# Sheet1.net
KiCad netlist of a schematic drawn in Altium Designer
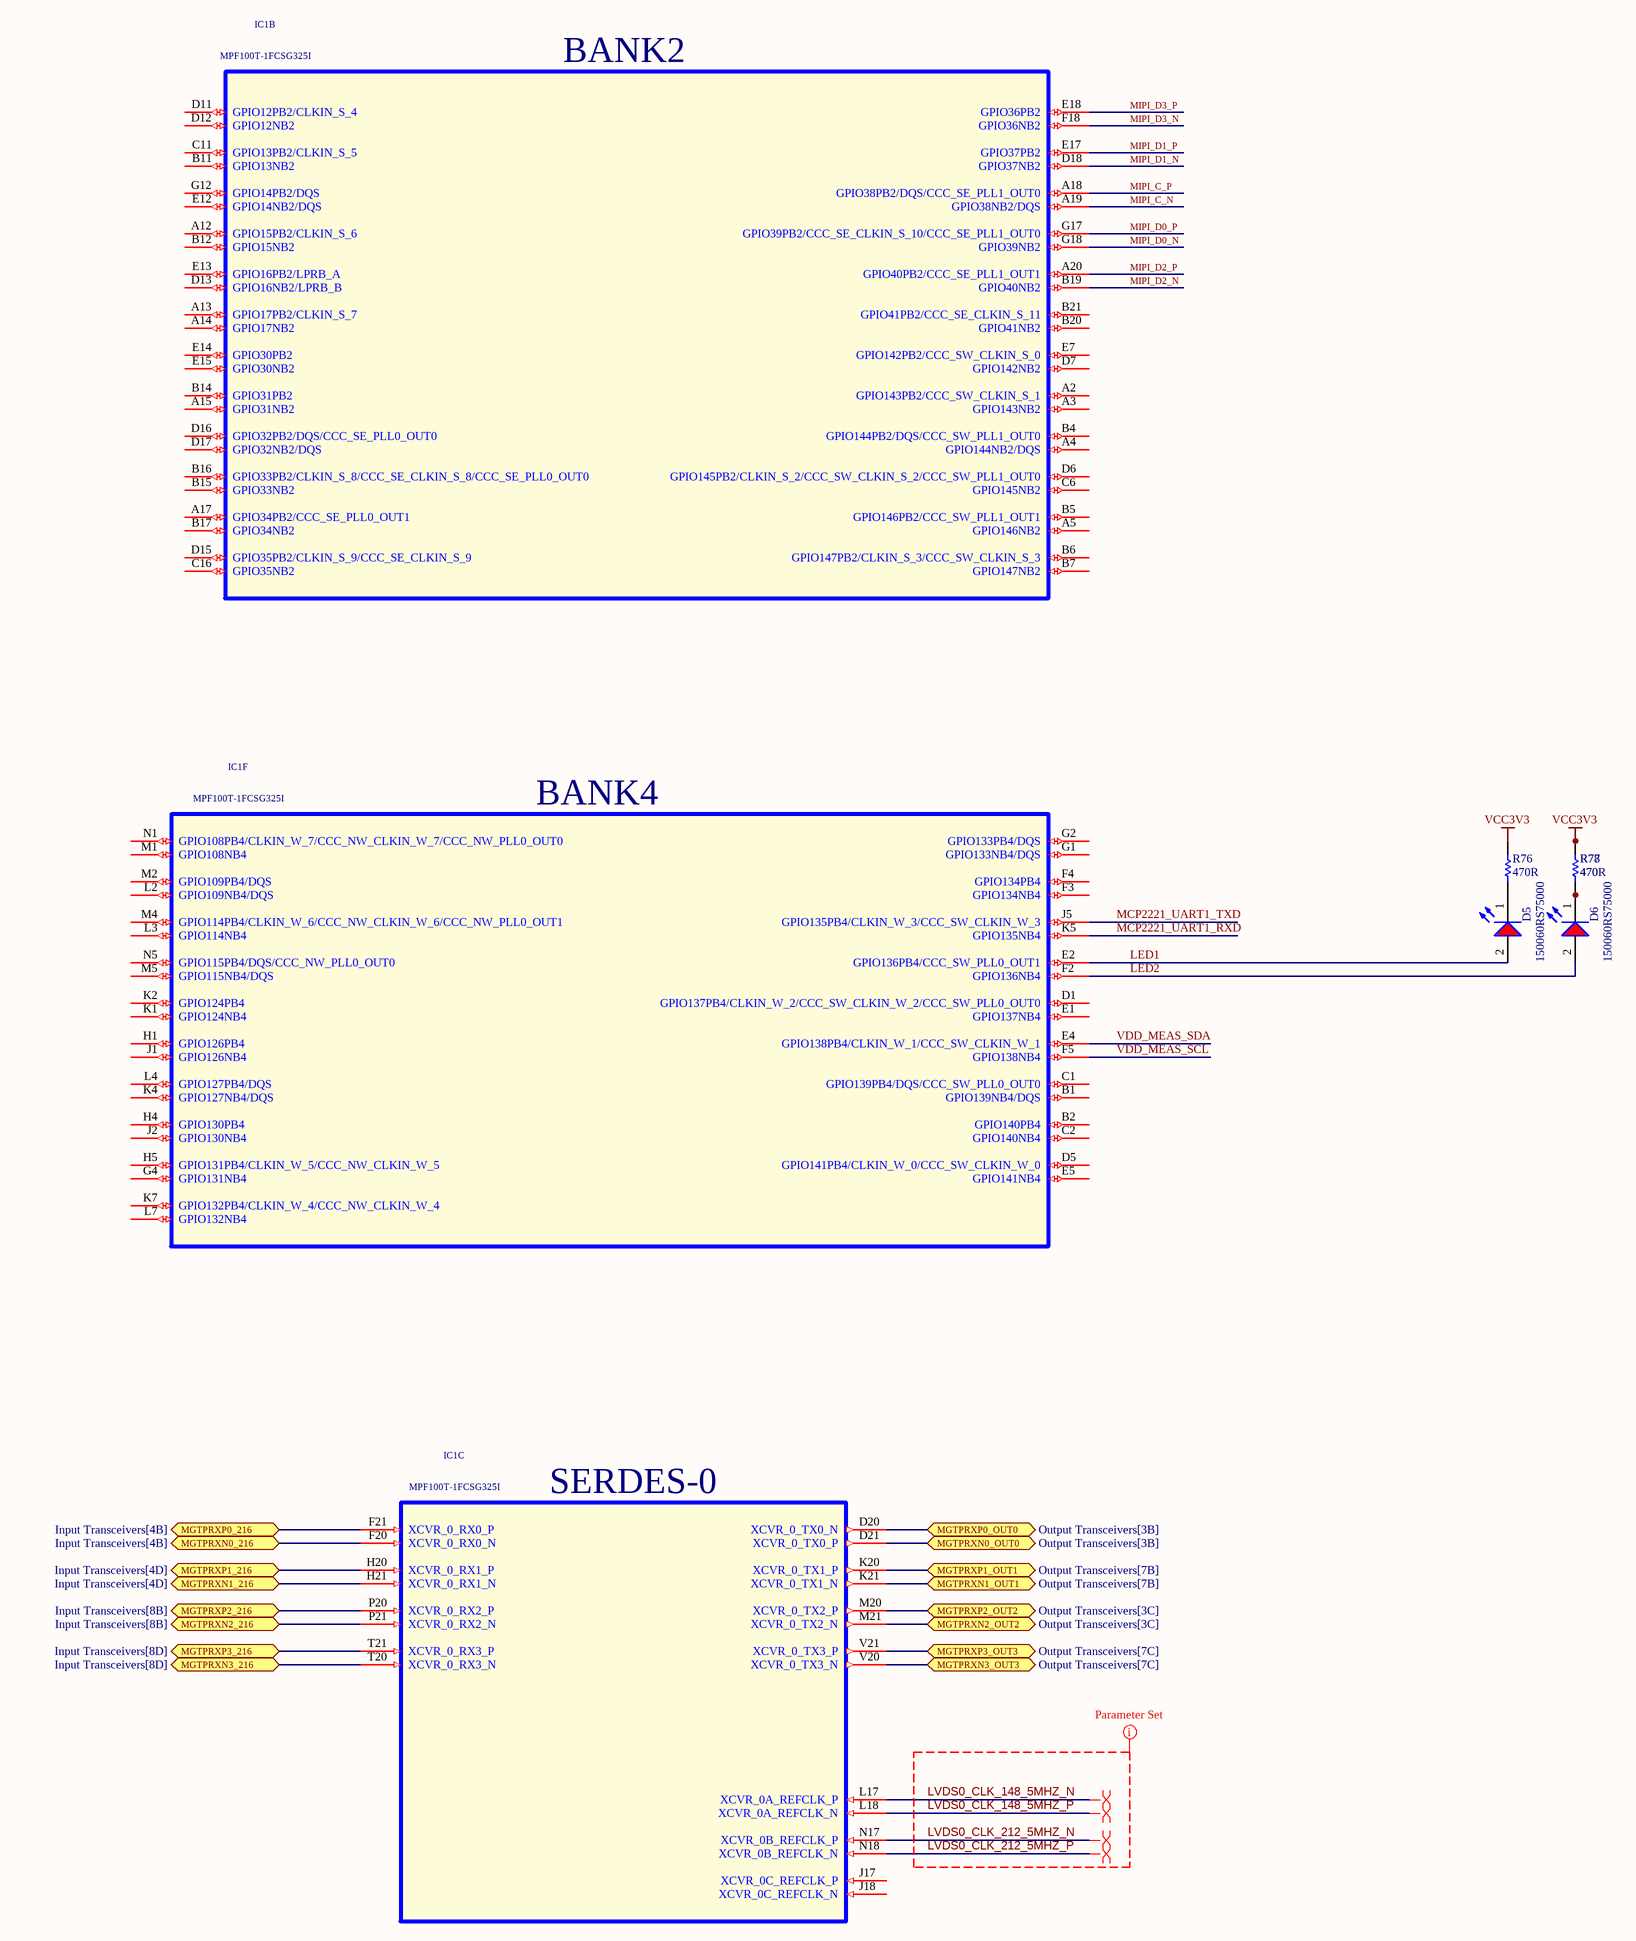
[diagram p0: Sheet1.schdoc]

(export (version "E")
  (design (tool "Eeschema 10.0.6"))
  (components
    (comp (ref "D5")
      (value "150060RS75000")
      (footprint "WL-SMCW_0603_150060xx75000")
      (description "LED Low-Power Uni-Color Red 630nm 2V 2-Pin Chip 0603(1608Metric) T/R")
      (libsource (lib "Altium Content Vault") (part "LED_Red_2A-1K"))
    )
    (comp (ref "D6")
      (value "150060RS75000")
      (footprint "WL-SMCW_0603_150060xx75000")
      (description "LED Low-Power Uni-Color Red 630nm 2V 2-Pin Chip 0603(1608Metric) T/R")
      (libsource (lib "Altium Content Vault") (part "LED_Red_2A-1K"))
    )
    (comp (ref "IC1")
      (value "MPF100T-1FCSG325I")
      (footprint "PCB_Display_Doru:MPF100T-1FCSG325I")
      (fields (field (name "PART_NUMBER") "J00001"))
      (libsource (lib "PCB_Display_Doru") (part "MPF100T-1FCSG325I"))
    )
    (comp (ref "R76")
      (value "470R")
      (footprint "RESC1005X40X25ML05T10")
      (fields (field (name "PART NUMBER") "RC0402FR-07470RL") (field (name "MANUFACTURER") "Yageo / Phycomp"))
      (libsource (lib "Altium Content Vault") (part "RES"))
    )
    (comp (ref "R77")
      (value "470")
      (footprint "RESC1005X40X25ML05T10")
      (fields (field (name "PART NUMBER") "RC0402FR-07470RL") (field (name "MANUFACTURER") "Yageo / Phycomp"))
      (libsource (lib "Altium Content Vault") (part "RES"))
    )
    (comp (ref "R78")
      (value "470R")
      (footprint "RESC1005X40X25ML05T10")
      (fields (field (name "PART NUMBER") "RC0402FR-07470RL") (field (name "MANUFACTURER") "Yageo / Phycomp"))
      (libsource (lib "Altium Content Vault") (part "RES"))
    )
  )
  (nets
    (net (code "1") (name "/LED1") (class "Default")
      (node (ref "D5") (pin "2") (pinfunction "A_2") (pintype "passive"))
      (node (ref "IC1") (pin "E2") (pinfunction "GPIO136PB4/CCC_SW_PLL0_OUT1_E2") (pintype "bidirectional"))
    )
    (net (code "2") (name "/LED2") (class "Default")
      (node (ref "D6") (pin "2") (pinfunction "A_2") (pintype "passive"))
      (node (ref "IC1") (pin "F2") (pinfunction "GPIO136NB4_F2") (pintype "bidirectional"))
    )
    (net (code "3") (name "/LVDS0_CLK_148_5MHZ_N") (class "Default")
      (node (ref "IC1") (pin "L17") (pinfunction "XCVR_0A_REFCLK_P_L17") (pintype "input"))
    )
    (net (code "4") (name "/LVDS0_CLK_148_5MHZ_P") (class "Default")
      (node (ref "IC1") (pin "L18") (pinfunction "XCVR_0A_REFCLK_N_L18") (pintype "input"))
    )
    (net (code "5") (name "/LVDS0_CLK_212_5MHZ_N") (class "Default")
      (node (ref "IC1") (pin "N17") (pinfunction "XCVR_0B_REFCLK_P_N17") (pintype "input"))
    )
    (net (code "6") (name "/LVDS0_CLK_212_5MHZ_P") (class "Default")
      (node (ref "IC1") (pin "N18") (pinfunction "XCVR_0B_REFCLK_N_N18") (pintype "input"))
    )
    (net (code "7") (name "/MCP2221_UART1_RXD") (class "Default")
      (node (ref "IC1") (pin "K5") (pinfunction "GPIO135NB4_K5") (pintype "bidirectional"))
    )
    (net (code "8") (name "/MCP2221_UART1_TXD") (class "Default")
      (node (ref "IC1") (pin "J5") (pinfunction "GPIO135PB4/CLKIN_W_3/CCC_SW_CLKIN_W_3_J5") (pintype "bidirectional"))
    )
    (net (code "9") (name "/MGTPRXN0_216") (class "Default")
      (node (ref "IC1") (pin "F20") (pinfunction "XCVR_0_RX0_N_F20") (pintype "input"))
    )
    (net (code "10") (name "/MGTPRXN0_OUT0") (class "Default")
      (node (ref "IC1") (pin "D21") (pinfunction "XCVR_0_TX0_P_D21") (pintype "output"))
    )
    (net (code "11") (name "/MGTPRXN1_216") (class "Default")
      (node (ref "IC1") (pin "H21") (pinfunction "XCVR_0_RX1_N_H21") (pintype "input"))
    )
    (net (code "12") (name "/MGTPRXN1_OUT1") (class "Default")
      (node (ref "IC1") (pin "K21") (pinfunction "XCVR_0_TX1_N_K21") (pintype "output"))
    )
    (net (code "13") (name "/MGTPRXN2_216") (class "Default")
      (node (ref "IC1") (pin "P21") (pinfunction "XCVR_0_RX2_N_P21") (pintype "input"))
    )
    (net (code "14") (name "/MGTPRXN2_OUT2") (class "Default")
      (node (ref "IC1") (pin "M21") (pinfunction "XCVR_0_TX2_N_M21") (pintype "output"))
    )
    (net (code "15") (name "/MGTPRXN3_216") (class "Default")
      (node (ref "IC1") (pin "T20") (pinfunction "XCVR_0_RX3_N_T20") (pintype "input"))
    )
    (net (code "16") (name "/MGTPRXN3_OUT3") (class "Default")
      (node (ref "IC1") (pin "V20") (pinfunction "XCVR_0_TX3_N_V20") (pintype "output"))
    )
    (net (code "17") (name "/MGTPRXP0_216") (class "Default")
      (node (ref "IC1") (pin "F21") (pinfunction "XCVR_0_RX0_P_F21") (pintype "input"))
    )
    (net (code "18") (name "/MGTPRXP0_OUT0") (class "Default")
      (node (ref "IC1") (pin "D20") (pinfunction "XCVR_0_TX0_N_D20") (pintype "output"))
    )
    (net (code "19") (name "/MGTPRXP1_216") (class "Default")
      (node (ref "IC1") (pin "H20") (pinfunction "XCVR_0_RX1_P_H20") (pintype "input"))
    )
    (net (code "20") (name "/MGTPRXP1_OUT1") (class "Default")
      (node (ref "IC1") (pin "K20") (pinfunction "XCVR_0_TX1_P_K20") (pintype "output"))
    )
    (net (code "21") (name "/MGTPRXP2_216") (class "Default")
      (node (ref "IC1") (pin "P20") (pinfunction "XCVR_0_RX2_P_P20") (pintype "input"))
    )
    (net (code "22") (name "/MGTPRXP2_OUT2") (class "Default")
      (node (ref "IC1") (pin "M20") (pinfunction "XCVR_0_TX2_P_M20") (pintype "output"))
    )
    (net (code "23") (name "/MGTPRXP3_216") (class "Default")
      (node (ref "IC1") (pin "T21") (pinfunction "XCVR_0_RX3_P_T21") (pintype "input"))
    )
    (net (code "24") (name "/MGTPRXP3_OUT3") (class "Default")
      (node (ref "IC1") (pin "V21") (pinfunction "XCVR_0_TX3_P_V21") (pintype "output"))
    )
    (net (code "25") (name "/MIPI_C_N") (class "Default")
      (node (ref "IC1") (pin "A19") (pinfunction "GPIO38NB2/DQS_A19") (pintype "bidirectional"))
    )
    (net (code "26") (name "/MIPI_C_P") (class "Default")
      (node (ref "IC1") (pin "A18") (pinfunction "GPIO38PB2/DQS/CCC_SE_PLL1_OUT0_A18") (pintype "bidirectional"))
    )
    (net (code "27") (name "/MIPI_D0_N") (class "Default")
      (node (ref "IC1") (pin "G18") (pinfunction "GPIO39NB2_G18") (pintype "bidirectional"))
    )
    (net (code "28") (name "/MIPI_D0_P") (class "Default")
      (node (ref "IC1") (pin "G17") (pinfunction "GPIO39PB2/CCC_SE_CLKIN_S_10/CCC_SE_PLL1_OUT0_G17") (pintype "bidirectional"))
    )
    (net (code "29") (name "/MIPI_D1_N") (class "Default")
      (node (ref "IC1") (pin "D18") (pinfunction "GPIO37NB2_D18") (pintype "bidirectional"))
    )
    (net (code "30") (name "/MIPI_D1_P") (class "Default")
      (node (ref "IC1") (pin "E17") (pinfunction "GPIO37PB2_E17") (pintype "bidirectional"))
    )
    (net (code "31") (name "/MIPI_D2_N") (class "Default")
      (node (ref "IC1") (pin "B19") (pinfunction "GPIO40NB2_B19") (pintype "bidirectional"))
    )
    (net (code "32") (name "/MIPI_D2_P") (class "Default")
      (node (ref "IC1") (pin "A20") (pinfunction "GPIO40PB2/CCC_SE_PLL1_OUT1_A20") (pintype "bidirectional"))
    )
    (net (code "33") (name "/MIPI_D3_N") (class "Default")
      (node (ref "IC1") (pin "F18") (pinfunction "GPIO36NB2_F18") (pintype "bidirectional"))
    )
    (net (code "34") (name "/MIPI_D3_P") (class "Default")
      (node (ref "IC1") (pin "E18") (pinfunction "GPIO36PB2_E18") (pintype "bidirectional"))
    )
    (net (code "35") (name "/VDD_MEAS_SCL") (class "Default")
      (node (ref "IC1") (pin "F5") (pinfunction "GPIO138NB4_F5") (pintype "bidirectional"))
    )
    (net (code "36") (name "/VDD_MEAS_SDA") (class "Default")
      (node (ref "IC1") (pin "E4") (pinfunction "GPIO138PB4/CLKIN_W_1/CCC_SW_CLKIN_W_1_E4") (pintype "bidirectional"))
    )
    (net (code "37") (name "Net-(D5-K)") (class "Default")
      (node (ref "D5") (pin "1") (pinfunction "K_1") (pintype "passive"))
      (node (ref "R76") (pin "1") (pinfunction "1_1") (pintype "passive"))
    )
    (net (code "38") (name "Net-(D6-K)") (class "Default")
      (node (ref "D6") (pin "1") (pinfunction "K_1") (pintype "passive"))
      (node (ref "R77") (pin "1") (pinfunction "1_1") (pintype "passive"))
      (node (ref "R78") (pin "1") (pinfunction "1_1") (pintype "passive"))
    )
    (net (code "39") (name "VCC3V3") (class "Default")
      (node (ref "R76") (pin "2") (pinfunction "2_2") (pintype "passive"))
      (node (ref "R77") (pin "2") (pinfunction "2_2") (pintype "passive"))
      (node (ref "R78") (pin "2") (pinfunction "2_2") (pintype "passive"))
    )
    (net (code "40") (name "unconnected-(IC1B-GPIO12NB2-PadD12)") (class "Default")
      (node (ref "IC1") (pin "D12") (pinfunction "GPIO12NB2_D12") (pintype "bidirectional"))
    )
    (net (code "41") (name "unconnected-(IC1B-GPIO12PB2{slash}CLKIN_S_4-PadD11)") (class "Default")
      (node (ref "IC1") (pin "D11") (pinfunction "GPIO12PB2/CLKIN_S_4_D11") (pintype "bidirectional"))
    )
    (net (code "42") (name "unconnected-(IC1B-GPIO13NB2-PadB11)") (class "Default")
      (node (ref "IC1") (pin "B11") (pinfunction "GPIO13NB2_B11") (pintype "bidirectional"))
    )
    (net (code "43") (name "unconnected-(IC1B-GPIO13PB2{slash}CLKIN_S_5-PadC11)") (class "Default")
      (node (ref "IC1") (pin "C11") (pinfunction "GPIO13PB2/CLKIN_S_5_C11") (pintype "bidirectional"))
    )
    (net (code "44") (name "unconnected-(IC1B-GPIO14NB2{slash}DQS-PadE12)") (class "Default")
      (node (ref "IC1") (pin "E12") (pinfunction "GPIO14NB2/DQS_E12") (pintype "bidirectional"))
    )
    (net (code "45") (name "unconnected-(IC1B-GPIO14PB2{slash}DQS-PadG12)") (class "Default")
      (node (ref "IC1") (pin "G12") (pinfunction "GPIO14PB2/DQS_G12") (pintype "bidirectional"))
    )
    (net (code "46") (name "unconnected-(IC1B-GPIO15NB2-PadB12)") (class "Default")
      (node (ref "IC1") (pin "B12") (pinfunction "GPIO15NB2_B12") (pintype "bidirectional"))
    )
    (net (code "47") (name "unconnected-(IC1B-GPIO15PB2{slash}CLKIN_S_6-PadA12)") (class "Default")
      (node (ref "IC1") (pin "A12") (pinfunction "GPIO15PB2/CLKIN_S_6_A12") (pintype "bidirectional"))
    )
    (net (code "48") (name "unconnected-(IC1B-GPIO16NB2{slash}LPRB_B-PadD13)") (class "Default")
      (node (ref "IC1") (pin "D13") (pinfunction "GPIO16NB2/LPRB_B_D13") (pintype "bidirectional"))
    )
    (net (code "49") (name "unconnected-(IC1B-GPIO16PB2{slash}LPRB_A-PadE13)") (class "Default")
      (node (ref "IC1") (pin "E13") (pinfunction "GPIO16PB2/LPRB_A_E13") (pintype "bidirectional"))
    )
    (net (code "50") (name "unconnected-(IC1B-GPIO17NB2-PadA14)") (class "Default")
      (node (ref "IC1") (pin "A14") (pinfunction "GPIO17NB2_A14") (pintype "bidirectional"))
    )
    (net (code "51") (name "unconnected-(IC1B-GPIO17PB2{slash}CLKIN_S_7-PadA13)") (class "Default")
      (node (ref "IC1") (pin "A13") (pinfunction "GPIO17PB2/CLKIN_S_7_A13") (pintype "bidirectional"))
    )
    (net (code "52") (name "unconnected-(IC1B-GPIO30NB2-PadE15)") (class "Default")
      (node (ref "IC1") (pin "E15") (pinfunction "GPIO30NB2_E15") (pintype "bidirectional"))
    )
    (net (code "53") (name "unconnected-(IC1B-GPIO30PB2-PadE14)") (class "Default")
      (node (ref "IC1") (pin "E14") (pinfunction "GPIO30PB2_E14") (pintype "bidirectional"))
    )
    (net (code "54") (name "unconnected-(IC1B-GPIO31NB2-PadA15)") (class "Default")
      (node (ref "IC1") (pin "A15") (pinfunction "GPIO31NB2_A15") (pintype "bidirectional"))
    )
    (net (code "55") (name "unconnected-(IC1B-GPIO31PB2-PadB14)") (class "Default")
      (node (ref "IC1") (pin "B14") (pinfunction "GPIO31PB2_B14") (pintype "bidirectional"))
    )
    (net (code "56") (name "unconnected-(IC1B-GPIO32NB2{slash}DQS-PadD17)") (class "Default")
      (node (ref "IC1") (pin "D17") (pinfunction "GPIO32NB2/DQS_D17") (pintype "bidirectional"))
    )
    (net (code "57") (name "unconnected-(IC1B-GPIO32PB2{slash}DQS{slash}CCC_SE_PLL0_OUT0-PadD16)") (class "Default")
      (node (ref "IC1") (pin "D16") (pinfunction "GPIO32PB2/DQS/CCC_SE_PLL0_OUT0_D16") (pintype "bidirectional"))
    )
    (net (code "58") (name "unconnected-(IC1B-GPIO33NB2-PadB15)") (class "Default")
      (node (ref "IC1") (pin "B15") (pinfunction "GPIO33NB2_B15") (pintype "bidirectional"))
    )
    (net (code "59") (name "unconnected-(IC1B-GPIO33PB2{slash}CLKIN_S_8{slash}CCC_SE_CLKIN_S_8{slash}CCC_SE_PLL0_OUT0-PadB16)") (class "Default")
      (node (ref "IC1") (pin "B16") (pinfunction "GPIO33PB2/CLKIN_S_8/CCC_SE_CLKIN_S_8/CCC_SE_PLL0_OUT0_B16") (pintype "bidirectional"))
    )
    (net (code "60") (name "unconnected-(IC1B-GPIO34NB2-PadB17)") (class "Default")
      (node (ref "IC1") (pin "B17") (pinfunction "GPIO34NB2_B17") (pintype "bidirectional"))
    )
    (net (code "61") (name "unconnected-(IC1B-GPIO34PB2{slash}CCC_SE_PLL0_OUT1-PadA17)") (class "Default")
      (node (ref "IC1") (pin "A17") (pinfunction "GPIO34PB2/CCC_SE_PLL0_OUT1_A17") (pintype "bidirectional"))
    )
    (net (code "62") (name "unconnected-(IC1B-GPIO35NB2-PadC16)") (class "Default")
      (node (ref "IC1") (pin "C16") (pinfunction "GPIO35NB2_C16") (pintype "bidirectional"))
    )
    (net (code "63") (name "unconnected-(IC1B-GPIO35PB2{slash}CLKIN_S_9{slash}CCC_SE_CLKIN_S_9-PadD15)") (class "Default")
      (node (ref "IC1") (pin "D15") (pinfunction "GPIO35PB2/CLKIN_S_9/CCC_SE_CLKIN_S_9_D15") (pintype "bidirectional"))
    )
    (net (code "64") (name "unconnected-(IC1B-GPIO41NB2-PadB20)") (class "Default")
      (node (ref "IC1") (pin "B20") (pinfunction "GPIO41NB2_B20") (pintype "bidirectional"))
    )
    (net (code "65") (name "unconnected-(IC1B-GPIO41PB2{slash}CCC_SE_CLKIN_S_11-PadB21)") (class "Default")
      (node (ref "IC1") (pin "B21") (pinfunction "GPIO41PB2/CCC_SE_CLKIN_S_11_B21") (pintype "bidirectional"))
    )
    (net (code "66") (name "unconnected-(IC1B-GPIO142NB2-PadD7)") (class "Default")
      (node (ref "IC1") (pin "D7") (pinfunction "GPIO142NB2_D7") (pintype "bidirectional"))
    )
    (net (code "67") (name "unconnected-(IC1B-GPIO142PB2{slash}CCC_SW_CLKIN_S_0-PadE7)") (class "Default")
      (node (ref "IC1") (pin "E7") (pinfunction "GPIO142PB2/CCC_SW_CLKIN_S_0_E7") (pintype "bidirectional"))
    )
    (net (code "68") (name "unconnected-(IC1B-GPIO143NB2-PadA3)") (class "Default")
      (node (ref "IC1") (pin "A3") (pinfunction "GPIO143NB2_A3") (pintype "bidirectional"))
    )
    (net (code "69") (name "unconnected-(IC1B-GPIO143PB2{slash}CCC_SW_CLKIN_S_1-PadA2)") (class "Default")
      (node (ref "IC1") (pin "A2") (pinfunction "GPIO143PB2/CCC_SW_CLKIN_S_1_A2") (pintype "bidirectional"))
    )
    (net (code "70") (name "unconnected-(IC1B-GPIO144NB2{slash}DQS-PadA4)") (class "Default")
      (node (ref "IC1") (pin "A4") (pinfunction "GPIO144NB2/DQS_A4") (pintype "bidirectional"))
    )
    (net (code "71") (name "unconnected-(IC1B-GPIO144PB2{slash}DQS{slash}CCC_SW_PLL1_OUT0-PadB4)") (class "Default")
      (node (ref "IC1") (pin "B4") (pinfunction "GPIO144PB2/DQS/CCC_SW_PLL1_OUT0_B4") (pintype "bidirectional"))
    )
    (net (code "72") (name "unconnected-(IC1B-GPIO145NB2-PadC6)") (class "Default")
      (node (ref "IC1") (pin "C6") (pinfunction "GPIO145NB2_C6") (pintype "bidirectional"))
    )
    (net (code "73") (name "unconnected-(IC1B-GPIO145PB2{slash}CLKIN_S_2{slash}CCC_SW_CLKIN_S_2{slash}CCC_SW_PLL1_OUT0-PadD6)") (class "Default")
      (node (ref "IC1") (pin "D6") (pinfunction "GPIO145PB2/CLKIN_S_2/CCC_SW_CLKIN_S_2/CCC_SW_PLL1_OUT0_D6") (pintype "bidirectional"))
    )
    (net (code "74") (name "unconnected-(IC1B-GPIO146NB2-PadA5)") (class "Default")
      (node (ref "IC1") (pin "A5") (pinfunction "GPIO146NB2_A5") (pintype "bidirectional"))
    )
    (net (code "75") (name "unconnected-(IC1B-GPIO146PB2{slash}CCC_SW_PLL1_OUT1-PadB5)") (class "Default")
      (node (ref "IC1") (pin "B5") (pinfunction "GPIO146PB2/CCC_SW_PLL1_OUT1_B5") (pintype "bidirectional"))
    )
    (net (code "76") (name "unconnected-(IC1B-GPIO147NB2-PadB7)") (class "Default")
      (node (ref "IC1") (pin "B7") (pinfunction "GPIO147NB2_B7") (pintype "bidirectional"))
    )
    (net (code "77") (name "unconnected-(IC1B-GPIO147PB2{slash}CLKIN_S_3{slash}CCC_SW_CLKIN_S_3-PadB6)") (class "Default")
      (node (ref "IC1") (pin "B6") (pinfunction "GPIO147PB2/CLKIN_S_3/CCC_SW_CLKIN_S_3_B6") (pintype "bidirectional"))
    )
    (net (code "78") (name "unconnected-(IC1C-XCVR_0C_REFCLK_N-PadJ18)") (class "Default")
      (node (ref "IC1") (pin "J18") (pinfunction "XCVR_0C_REFCLK_N_J18") (pintype "input"))
    )
    (net (code "79") (name "unconnected-(IC1C-XCVR_0C_REFCLK_P-PadJ17)") (class "Default")
      (node (ref "IC1") (pin "J17") (pinfunction "XCVR_0C_REFCLK_P_J17") (pintype "input"))
    )
    (net (code "80") (name "unconnected-(IC1F-GPIO108NB4-PadM1)") (class "Default")
      (node (ref "IC1") (pin "M1") (pinfunction "GPIO108NB4_M1") (pintype "bidirectional"))
    )
    (net (code "81") (name "unconnected-(IC1F-GPIO108PB4{slash}CLKIN_W_7{slash}CCC_NW_CLKIN_W_7{slash}CCC_NW_PLL0_OUT0-PadN1)") (class "Default")
      (node (ref "IC1") (pin "N1") (pinfunction "GPIO108PB4/CLKIN_W_7/CCC_NW_CLKIN_W_7/CCC_NW_PLL0_OUT0_N1") (pintype "bidirectional"))
    )
    (net (code "82") (name "unconnected-(IC1F-GPIO109NB4{slash}DQS-PadL2)") (class "Default")
      (node (ref "IC1") (pin "L2") (pinfunction "GPIO109NB4/DQS_L2") (pintype "bidirectional"))
    )
    (net (code "83") (name "unconnected-(IC1F-GPIO109PB4{slash}DQS-PadM2)") (class "Default")
      (node (ref "IC1") (pin "M2") (pinfunction "GPIO109PB4/DQS_M2") (pintype "bidirectional"))
    )
    (net (code "84") (name "unconnected-(IC1F-GPIO114NB4-PadL3)") (class "Default")
      (node (ref "IC1") (pin "L3") (pinfunction "GPIO114NB4_L3") (pintype "bidirectional"))
    )
    (net (code "85") (name "unconnected-(IC1F-GPIO114PB4{slash}CLKIN_W_6{slash}CCC_NW_CLKIN_W_6{slash}CCC_NW_PLL0_OUT1-PadM4)") (class "Default")
      (node (ref "IC1") (pin "M4") (pinfunction "GPIO114PB4/CLKIN_W_6/CCC_NW_CLKIN_W_6/CCC_NW_PLL0_OUT1_M4") (pintype "bidirectional"))
    )
    (net (code "86") (name "unconnected-(IC1F-GPIO115NB4{slash}DQS-PadM5)") (class "Default")
      (node (ref "IC1") (pin "M5") (pinfunction "GPIO115NB4/DQS_M5") (pintype "bidirectional"))
    )
    (net (code "87") (name "unconnected-(IC1F-GPIO115PB4{slash}DQS{slash}CCC_NW_PLL0_OUT0-PadN5)") (class "Default")
      (node (ref "IC1") (pin "N5") (pinfunction "GPIO115PB4/DQS/CCC_NW_PLL0_OUT0_N5") (pintype "bidirectional"))
    )
    (net (code "88") (name "unconnected-(IC1F-GPIO124NB4-PadK1)") (class "Default")
      (node (ref "IC1") (pin "K1") (pinfunction "GPIO124NB4_K1") (pintype "bidirectional"))
    )
    (net (code "89") (name "unconnected-(IC1F-GPIO124PB4-PadK2)") (class "Default")
      (node (ref "IC1") (pin "K2") (pinfunction "GPIO124PB4_K2") (pintype "bidirectional"))
    )
    (net (code "90") (name "unconnected-(IC1F-GPIO126NB4-PadJ1)") (class "Default")
      (node (ref "IC1") (pin "J1") (pinfunction "GPIO126NB4_J1") (pintype "bidirectional"))
    )
    (net (code "91") (name "unconnected-(IC1F-GPIO126PB4-PadH1)") (class "Default")
      (node (ref "IC1") (pin "H1") (pinfunction "GPIO126PB4_H1") (pintype "bidirectional"))
    )
    (net (code "92") (name "unconnected-(IC1F-GPIO127NB4{slash}DQS-PadK4)") (class "Default")
      (node (ref "IC1") (pin "K4") (pinfunction "GPIO127NB4/DQS_K4") (pintype "bidirectional"))
    )
    (net (code "93") (name "unconnected-(IC1F-GPIO127PB4{slash}DQS-PadL4)") (class "Default")
      (node (ref "IC1") (pin "L4") (pinfunction "GPIO127PB4/DQS_L4") (pintype "bidirectional"))
    )
    (net (code "94") (name "unconnected-(IC1F-GPIO130NB4-PadJ2)") (class "Default")
      (node (ref "IC1") (pin "J2") (pinfunction "GPIO130NB4_J2") (pintype "bidirectional"))
    )
    (net (code "95") (name "unconnected-(IC1F-GPIO130PB4-PadH4)") (class "Default")
      (node (ref "IC1") (pin "H4") (pinfunction "GPIO130PB4_H4") (pintype "bidirectional"))
    )
    (net (code "96") (name "unconnected-(IC1F-GPIO131NB4-PadG4)") (class "Default")
      (node (ref "IC1") (pin "G4") (pinfunction "GPIO131NB4_G4") (pintype "bidirectional"))
    )
    (net (code "97") (name "unconnected-(IC1F-GPIO131PB4{slash}CLKIN_W_5{slash}CCC_NW_CLKIN_W_5-PadH5)") (class "Default")
      (node (ref "IC1") (pin "H5") (pinfunction "GPIO131PB4/CLKIN_W_5/CCC_NW_CLKIN_W_5_H5") (pintype "bidirectional"))
    )
    (net (code "98") (name "unconnected-(IC1F-GPIO132NB4-PadL7)") (class "Default")
      (node (ref "IC1") (pin "L7") (pinfunction "GPIO132NB4_L7") (pintype "bidirectional"))
    )
    (net (code "99") (name "unconnected-(IC1F-GPIO132PB4{slash}CLKIN_W_4{slash}CCC_NW_CLKIN_W_4-PadK7)") (class "Default")
      (node (ref "IC1") (pin "K7") (pinfunction "GPIO132PB4/CLKIN_W_4/CCC_NW_CLKIN_W_4_K7") (pintype "bidirectional"))
    )
    (net (code "100") (name "unconnected-(IC1F-GPIO133NB4{slash}DQS-PadG1)") (class "Default")
      (node (ref "IC1") (pin "G1") (pinfunction "GPIO133NB4/DQS_G1") (pintype "bidirectional"))
    )
    (net (code "101") (name "unconnected-(IC1F-GPIO133PB4{slash}DQS-PadG2)") (class "Default")
      (node (ref "IC1") (pin "G2") (pinfunction "GPIO133PB4/DQS_G2") (pintype "bidirectional"))
    )
    (net (code "102") (name "unconnected-(IC1F-GPIO134NB4-PadF3)") (class "Default")
      (node (ref "IC1") (pin "F3") (pinfunction "GPIO134NB4_F3") (pintype "bidirectional"))
    )
    (net (code "103") (name "unconnected-(IC1F-GPIO134PB4-PadF4)") (class "Default")
      (node (ref "IC1") (pin "F4") (pinfunction "GPIO134PB4_F4") (pintype "bidirectional"))
    )
    (net (code "104") (name "unconnected-(IC1F-GPIO137NB4-PadE1)") (class "Default")
      (node (ref "IC1") (pin "E1") (pinfunction "GPIO137NB4_E1") (pintype "bidirectional"))
    )
    (net (code "105") (name "unconnected-(IC1F-GPIO137PB4{slash}CLKIN_W_2{slash}CCC_SW_CLKIN_W_2{slash}CCC_SW_PLL0_OUT0-PadD1)") (class "Default")
      (node (ref "IC1") (pin "D1") (pinfunction "GPIO137PB4/CLKIN_W_2/CCC_SW_CLKIN_W_2/CCC_SW_PLL0_OUT0_D1") (pintype "bidirectional"))
    )
    (net (code "106") (name "unconnected-(IC1F-GPIO139NB4{slash}DQS-PadB1)") (class "Default")
      (node (ref "IC1") (pin "B1") (pinfunction "GPIO139NB4/DQS_B1") (pintype "bidirectional"))
    )
    (net (code "107") (name "unconnected-(IC1F-GPIO139PB4{slash}DQS{slash}CCC_SW_PLL0_OUT0-PadC1)") (class "Default")
      (node (ref "IC1") (pin "C1") (pinfunction "GPIO139PB4/DQS/CCC_SW_PLL0_OUT0_C1") (pintype "bidirectional"))
    )
    (net (code "108") (name "unconnected-(IC1F-GPIO140NB4-PadC2)") (class "Default")
      (node (ref "IC1") (pin "C2") (pinfunction "GPIO140NB4_C2") (pintype "bidirectional"))
    )
    (net (code "109") (name "unconnected-(IC1F-GPIO140PB4-PadB2)") (class "Default")
      (node (ref "IC1") (pin "B2") (pinfunction "GPIO140PB4_B2") (pintype "bidirectional"))
    )
    (net (code "110") (name "unconnected-(IC1F-GPIO141NB4-PadE5)") (class "Default")
      (node (ref "IC1") (pin "E5") (pinfunction "GPIO141NB4_E5") (pintype "bidirectional"))
    )
    (net (code "111") (name "unconnected-(IC1F-GPIO141PB4{slash}CLKIN_W_0{slash}CCC_SW_CLKIN_W_0-PadD5)") (class "Default")
      (node (ref "IC1") (pin "D5") (pinfunction "GPIO141PB4/CLKIN_W_0/CCC_SW_CLKIN_W_0_D5") (pintype "bidirectional"))
    )
  )
)
